# 485_termination.net
KiCad netlist of a schematic drawn in Altium Designer
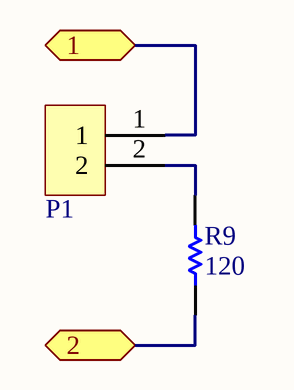
[diagram p0: 485_termination.SchDoc]

(export (version "E")
  (design (tool "Eeschema 10.0.6"))
  (components
    (comp (ref "P1")
      (value "TE Connectivity 3-644456-2")
      (footprint "PCB-5yupddsicqn8qq7gr5lb-1")
      (libsource (lib "CommunityVault") (part "CMP-2a80e1d15423f547-28"))
    )
    (comp (ref "R9")
      (value "120")
      (footprint "RESC1609X50X30LL8T20")
      (description "Chip Resistor, 120 Ohm, +/- 1%, 100 mW, -55 to 155 degC, 0603 (1608 Metric), RoHS, Tape and Reel")
      (fields (field (name "MANUFACTURER PART NUMBER") "CRCW0603120RFKEA"))
      (libsource (lib "CommunityVault") (part "CMP-1873454-4"))
    )
  )
  (nets
    (net (code "1") (name "/1") (class "Default")
      (node (ref "P1") (pin "1") (pinfunction "1_1") (pintype "passive"))
    )
    (net (code "2") (name "/2") (class "Default")
      (node (ref "R9") (pin "1") (pinfunction "1_1") (pintype "passive"))
    )
    (net (code "3") (name "Net-(P1-Pad2)") (class "Default")
      (node (ref "P1") (pin "2") (pinfunction "2_2") (pintype "passive"))
      (node (ref "R9") (pin "2") (pinfunction "2_2") (pintype "passive"))
    )
  )
)
